# G008A.net
KiCad netlist of a schematic drawn in EAGLE
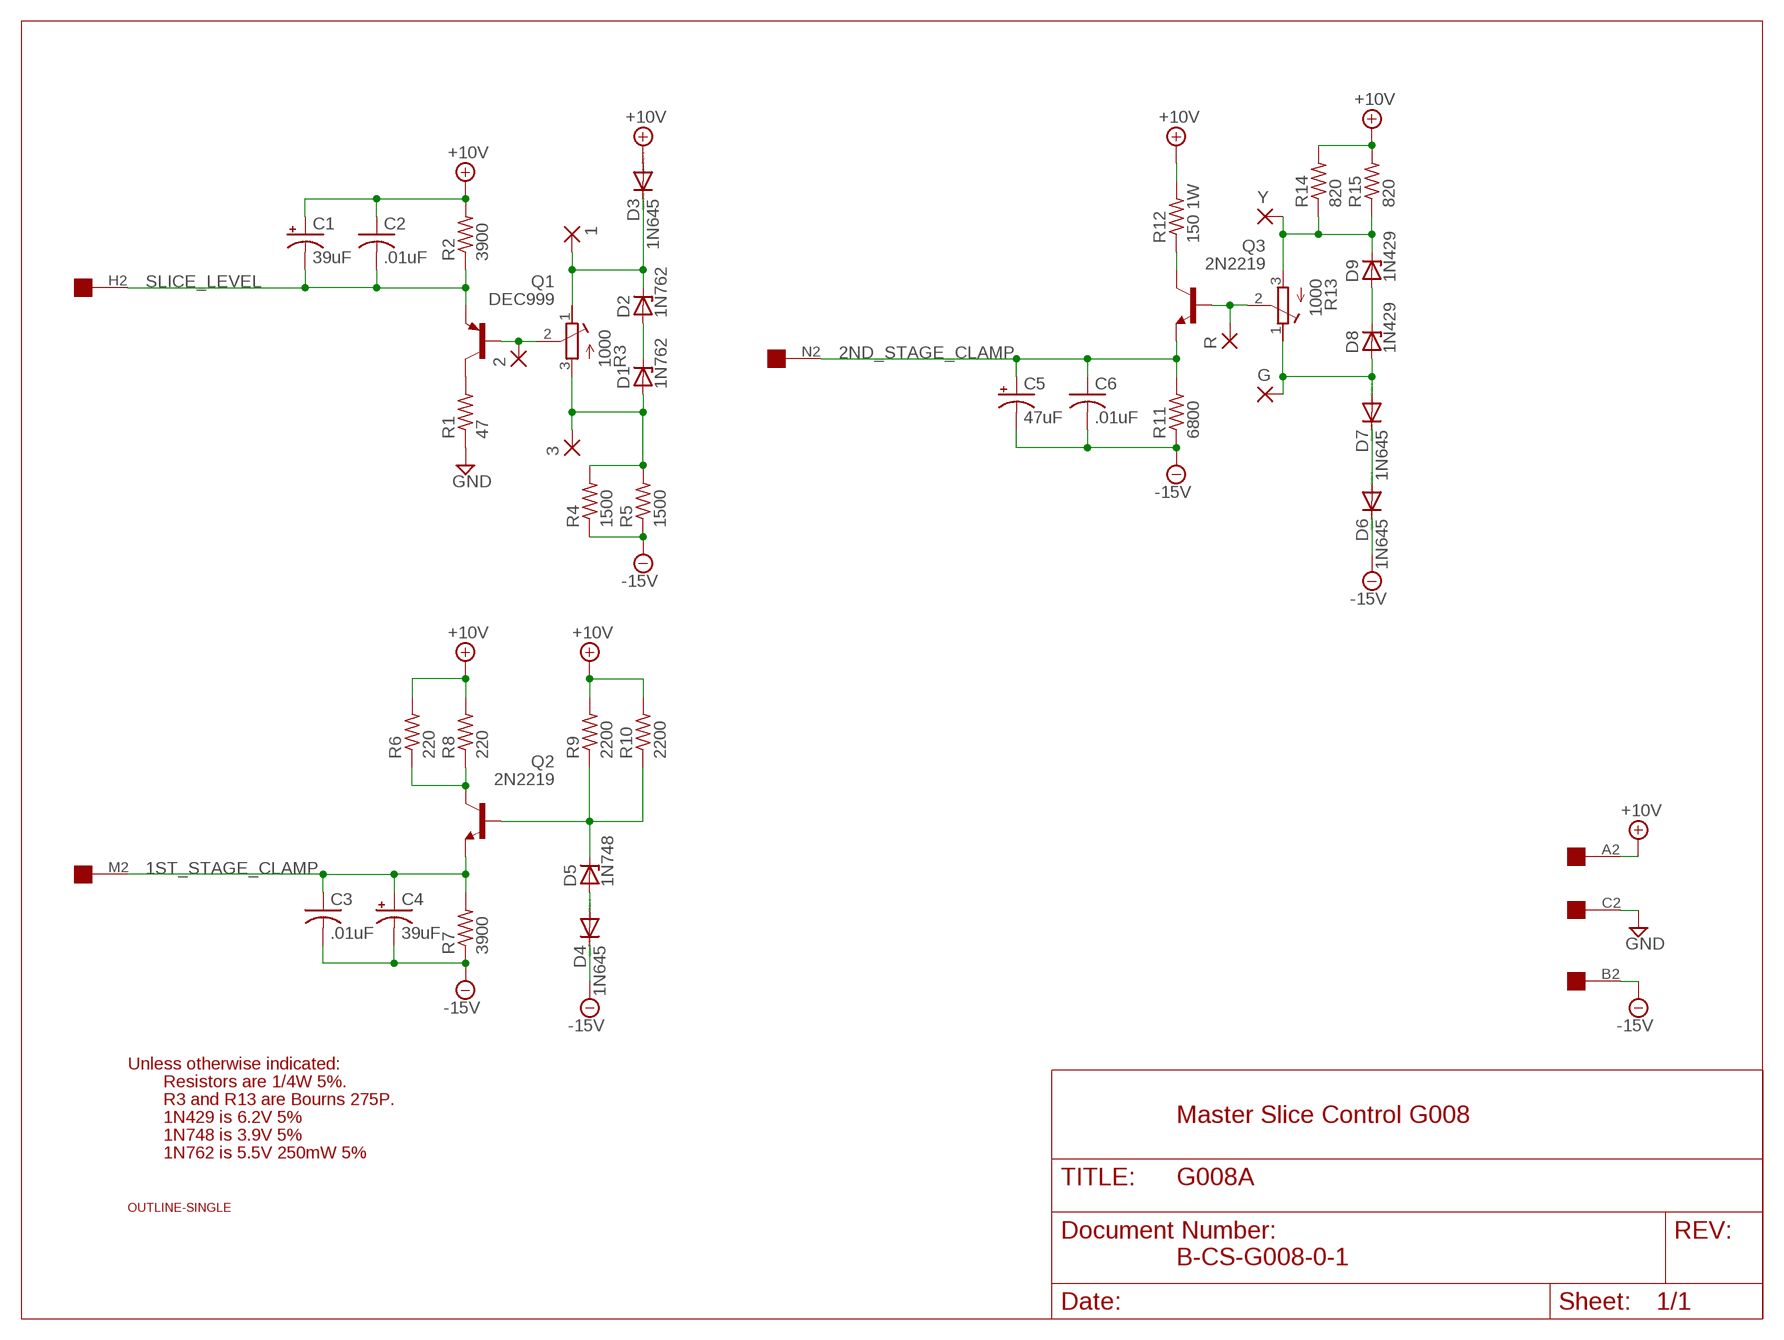
[diagram p0: schematic, sheet 1]

(export (version "E")
  (design (tool "Eeschema 10.0.6"))
  (components
    (comp (ref "1")
      (value "2,54/0,8")
      (footprint "eagle-import:2,54_0,8")
      (libsource (lib "eagle-import") (part "2,54/0,8"))
    )
    (comp (ref "2")
      (value "2,54/0,8")
      (footprint "eagle-import:2,54_0,8")
      (libsource (lib "eagle-import") (part "2,54/0,8"))
    )
    (comp (ref "3")
      (value "2,54/0,8")
      (footprint "eagle-import:2,54_0,8")
      (libsource (lib "eagle-import") (part "2,54/0,8"))
    )
    (comp (ref "C1")
      (value "39uF")
      (footprint "eagle-import:E15-5")
      (libsource (lib "eagle-import") (part "CPOL-USE15-5AXIAL"))
    )
    (comp (ref "C2")
      (value ".01uF")
      (footprint "eagle-import:C050-025X075")
      (libsource (lib "eagle-import") (part "C-US050-025X075"))
    )
    (comp (ref "C3")
      (value ".01uF")
      (footprint "eagle-import:C050-025X075")
      (libsource (lib "eagle-import") (part "C-US050-025X075"))
    )
    (comp (ref "C4")
      (value "39uF")
      (footprint "eagle-import:E15-5")
      (libsource (lib "eagle-import") (part "CPOL-USE15-5AXIAL"))
    )
    (comp (ref "C5")
      (value "47uF")
      (footprint "eagle-import:E22-6")
      (libsource (lib "eagle-import") (part "CPOL-USE22-6AXIAL"))
    )
    (comp (ref "C6")
      (value ".01uF")
      (footprint "eagle-import:C050-025X075")
      (libsource (lib "eagle-import") (part "C-US050-025X075"))
    )
    (comp (ref "D1")
      (value "1N762")
      (footprint "eagle-import:DO35Z10")
      (libsource (lib "eagle-import") (part "ZENER-DIODEDO35Z10"))
    )
    (comp (ref "D2")
      (value "1N762")
      (footprint "eagle-import:DO35Z10")
      (libsource (lib "eagle-import") (part "ZENER-DIODEDO35Z10"))
    )
    (comp (ref "D3")
      (value "1N645")
      (footprint "eagle-import:DO35-10")
      (libsource (lib "eagle-import") (part "1N4148DO35-10"))
    )
    (comp (ref "D4")
      (value "1N645")
      (footprint "eagle-import:DO35-10")
      (libsource (lib "eagle-import") (part "1N4148DO35-10"))
    )
    (comp (ref "D5")
      (value "1N748")
      (footprint "eagle-import:DO35Z10")
      (libsource (lib "eagle-import") (part "ZENER-DIODEDO35Z10"))
    )
    (comp (ref "D6")
      (value "1N645")
      (footprint "eagle-import:DO35-10")
      (libsource (lib "eagle-import") (part "1N4148DO35-10"))
    )
    (comp (ref "D7")
      (value "1N645")
      (footprint "eagle-import:DO35-10")
      (libsource (lib "eagle-import") (part "1N4148DO35-10"))
    )
    (comp (ref "D8")
      (value "1N429")
      (footprint "eagle-import:DO35Z10")
      (libsource (lib "eagle-import") (part "ZENER-DIODEDO35Z10"))
    )
    (comp (ref "D9")
      (value "1N429")
      (footprint "eagle-import:DO35Z10")
      (libsource (lib "eagle-import") (part "ZENER-DIODEDO35Z10"))
    )
    (comp (ref "G")
      (value "2,54/0,8")
      (footprint "eagle-import:2,54_0,8")
      (libsource (lib "eagle-import") (part "2,54/0,8"))
    )
    (comp (ref "Q1")
      (value "DEC999")
      (footprint "eagle-import:TO39")
      (libsource (lib "eagle-import") (part "2N2904"))
    )
    (comp (ref "Q2")
      (value "2N2219")
      (footprint "eagle-import:TO5")
      (libsource (lib "eagle-import") (part "2N2102"))
    )
    (comp (ref "Q3")
      (value "2N2219")
      (footprint "eagle-import:TO5")
      (libsource (lib "eagle-import") (part "2N2102"))
    )
    (comp (ref "R")
      (value "2,54/0,8")
      (footprint "eagle-import:2,54_0,8")
      (libsource (lib "eagle-import") (part "2,54/0,8"))
    )
    (comp (ref "R1")
      (value "47")
      (footprint "eagle-import:0207_10")
      (libsource (lib "eagle-import") (part "R-US_0207/10"))
    )
    (comp (ref "R2")
      (value "3900")
      (footprint "eagle-import:0207_10")
      (libsource (lib "eagle-import") (part "R-US_0207/10"))
    )
    (comp (ref "R3")
      (value "1000")
      (footprint "eagle-import:3006Y")
      (libsource (lib "eagle-import") (part "275P"))
    )
    (comp (ref "R4")
      (value "1500")
      (footprint "eagle-import:0207_10")
      (libsource (lib "eagle-import") (part "R-US_0207/10"))
    )
    (comp (ref "R5")
      (value "1500")
      (footprint "eagle-import:0207_10")
      (libsource (lib "eagle-import") (part "R-US_0207/10"))
    )
    (comp (ref "R6")
      (value "220")
      (footprint "eagle-import:0207_10")
      (libsource (lib "eagle-import") (part "R-US_0207/10"))
    )
    (comp (ref "R7")
      (value "3900")
      (footprint "eagle-import:0207_10")
      (libsource (lib "eagle-import") (part "R-US_0207/10"))
    )
    (comp (ref "R8")
      (value "220")
      (footprint "eagle-import:0207_10")
      (libsource (lib "eagle-import") (part "R-US_0207/10"))
    )
    (comp (ref "R9")
      (value "2200")
      (footprint "eagle-import:0207_10")
      (libsource (lib "eagle-import") (part "R-US_0207/10"))
    )
    (comp (ref "R10")
      (value "2200")
      (footprint "eagle-import:0207_10")
      (libsource (lib "eagle-import") (part "R-US_0207/10"))
    )
    (comp (ref "R11")
      (value "6800")
      (footprint "eagle-import:0207_10")
      (libsource (lib "eagle-import") (part "R-US_0207/10"))
    )
    (comp (ref "R12")
      (value "150 1W")
      (footprint "eagle-import:0617_22")
      (libsource (lib "eagle-import") (part "R-US_0617/22"))
    )
    (comp (ref "R13")
      (value "1000")
      (footprint "eagle-import:3006Y")
      (libsource (lib "eagle-import") (part "275P"))
    )
    (comp (ref "R14")
      (value "820")
      (footprint "eagle-import:0207_10")
      (libsource (lib "eagle-import") (part "R-US_0207/10"))
    )
    (comp (ref "R15")
      (value "820")
      (footprint "eagle-import:0207_10")
      (libsource (lib "eagle-import") (part "R-US_0207/10"))
    )
    (comp (ref "U$1")
      (value "OUTLINE-SINGLE")
      (footprint "eagle-import:SINGLE")
      (libsource (lib "eagle-import") (part "OUTLINE-SINGLE"))
    )
    (comp (ref "U$2")
      (value "EDGE-1")
      (footprint "eagle-import:EDGE-CON1")
      (libsource (lib "eagle-import") (part "EDGE-1"))
    )
    (comp (ref "Y")
      (value "2,54/0,8")
      (footprint "eagle-import:2,54_0,8")
      (libsource (lib "eagle-import") (part "2,54/0,8"))
    )
  )
  (nets
    (net (code "1") (name "+10V") (class "Default")
      (node (ref "C1") (pin "+") (pinfunction "+_+") (pintype "passive"))
      (node (ref "C2") (pin "1") (pinfunction "1_1") (pintype "passive"))
      (node (ref "D3") (pin "A") (pinfunction "A_A") (pintype "passive"))
      (node (ref "R10") (pin "2") (pinfunction "2_2") (pintype "passive"))
      (node (ref "R12") (pin "2") (pinfunction "2_2") (pintype "passive"))
      (node (ref "R14") (pin "2") (pinfunction "2_2") (pintype "passive"))
      (node (ref "R15") (pin "2") (pinfunction "2_2") (pintype "passive"))
      (node (ref "R2") (pin "2") (pinfunction "2_2") (pintype "passive"))
      (node (ref "R6") (pin "2") (pinfunction "2_2") (pintype "passive"))
      (node (ref "R8") (pin "2") (pinfunction "2_2") (pintype "passive"))
      (node (ref "R9") (pin "2") (pinfunction "2_2") (pintype "passive"))
      (node (ref "U$2") (pin "A2") (pinfunction "1_A2") (pintype "bidirectional"))
    )
    (net (code "2") (name "-15V") (class "Default")
      (node (ref "C3") (pin "2") (pinfunction "2_2") (pintype "passive"))
      (node (ref "C4") (pin "-") (pinfunction "-_-") (pintype "passive"))
      (node (ref "C5") (pin "-") (pinfunction "-_-") (pintype "passive"))
      (node (ref "C6") (pin "2") (pinfunction "2_2") (pintype "passive"))
      (node (ref "D4") (pin "C") (pinfunction "C_C") (pintype "passive"))
      (node (ref "D6") (pin "C") (pinfunction "C_C") (pintype "passive"))
      (node (ref "R11") (pin "1") (pinfunction "1_1") (pintype "passive"))
      (node (ref "R4") (pin "1") (pinfunction "1_1") (pintype "passive"))
      (node (ref "R5") (pin "1") (pinfunction "1_1") (pintype "passive"))
      (node (ref "R7") (pin "1") (pinfunction "1_1") (pintype "passive"))
      (node (ref "U$2") (pin "B2") (pinfunction "1_B2") (pintype "bidirectional"))
    )
    (net (code "3") (name "/1ST_STAGE_CLAMP") (class "Default")
      (node (ref "C3") (pin "1") (pinfunction "1_1") (pintype "passive"))
      (node (ref "C4") (pin "+") (pinfunction "+_+") (pintype "passive"))
      (node (ref "Q2") (pin "1") (pinfunction "E_1") (pintype "passive"))
      (node (ref "R7") (pin "2") (pinfunction "2_2") (pintype "passive"))
      (node (ref "U$2") (pin "M2") (pinfunction "1_M2") (pintype "bidirectional"))
    )
    (net (code "4") (name "/2ND_STAGE_CLAMP") (class "Default")
      (node (ref "C5") (pin "+") (pinfunction "+_+") (pintype "passive"))
      (node (ref "C6") (pin "1") (pinfunction "1_1") (pintype "passive"))
      (node (ref "Q3") (pin "1") (pinfunction "E_1") (pintype "passive"))
      (node (ref "R11") (pin "2") (pinfunction "2_2") (pintype "passive"))
      (node (ref "U$2") (pin "N2") (pinfunction "1_N2") (pintype "bidirectional"))
    )
    (net (code "5") (name "/SLICE_LEVEL") (class "Default")
      (node (ref "C1") (pin "-") (pinfunction "-_-") (pintype "passive"))
      (node (ref "C2") (pin "2") (pinfunction "2_2") (pintype "passive"))
      (node (ref "Q1") (pin "1") (pinfunction "E_1") (pintype "passive"))
      (node (ref "R2") (pin "1") (pinfunction "1_1") (pintype "passive"))
      (node (ref "U$2") (pin "H2") (pinfunction "1_H2") (pintype "bidirectional"))
    )
    (net (code "6") (name "GND") (class "Default")
      (node (ref "R1") (pin "1") (pinfunction "1_1") (pintype "passive"))
      (node (ref "U$2") (pin "C2") (pinfunction "1_C2") (pintype "bidirectional"))
    )
    (net (code "7") (name "Net-(1-P)") (class "Default")
      (node (ref "1") (pin "1") (pinfunction "P_1") (pintype "passive"))
      (node (ref "D2") (pin "C") (pinfunction "C_C") (pintype "passive"))
      (node (ref "D3") (pin "C") (pinfunction "C_C") (pintype "passive"))
      (node (ref "R3") (pin "1") (pinfunction "A_1") (pintype "passive"))
    )
    (net (code "8") (name "Net-(2-P)") (class "Default")
      (node (ref "2") (pin "1") (pinfunction "P_1") (pintype "passive"))
      (node (ref "Q1") (pin "2") (pinfunction "B_2") (pintype "passive"))
      (node (ref "R3") (pin "2") (pinfunction "S_2") (pintype "passive"))
    )
    (net (code "9") (name "Net-(3-P)") (class "Default")
      (node (ref "3") (pin "1") (pinfunction "P_1") (pintype "passive"))
      (node (ref "D1") (pin "A") (pinfunction "A_A") (pintype "passive"))
      (node (ref "R3") (pin "3") (pinfunction "E_3") (pintype "passive"))
      (node (ref "R4") (pin "2") (pinfunction "2_2") (pintype "passive"))
      (node (ref "R5") (pin "2") (pinfunction "2_2") (pintype "passive"))
    )
    (net (code "10") (name "Net-(D1-PadC)") (class "Default")
      (node (ref "D1") (pin "C") (pinfunction "C_C") (pintype "passive"))
      (node (ref "D2") (pin "A") (pinfunction "A_A") (pintype "passive"))
    )
    (net (code "11") (name "Net-(D4-PadA)") (class "Default")
      (node (ref "D4") (pin "A") (pinfunction "A_A") (pintype "passive"))
      (node (ref "D5") (pin "A") (pinfunction "A_A") (pintype "passive"))
    )
    (net (code "12") (name "Net-(D6-PadA)") (class "Default")
      (node (ref "D6") (pin "A") (pinfunction "A_A") (pintype "passive"))
      (node (ref "D7") (pin "C") (pinfunction "C_C") (pintype "passive"))
    )
    (net (code "13") (name "Net-(D8-PadC)") (class "Default")
      (node (ref "D8") (pin "C") (pinfunction "C_C") (pintype "passive"))
      (node (ref "D9") (pin "A") (pinfunction "A_A") (pintype "passive"))
    )
    (net (code "14") (name "Net-(G-P)") (class "Default")
      (node (ref "D7") (pin "A") (pinfunction "A_A") (pintype "passive"))
      (node (ref "D8") (pin "A") (pinfunction "A_A") (pintype "passive"))
      (node (ref "G") (pin "1") (pinfunction "P_1") (pintype "passive"))
      (node (ref "R13") (pin "1") (pinfunction "A_1") (pintype "passive"))
    )
    (net (code "15") (name "Net-(Q1-C)") (class "Default")
      (node (ref "Q1") (pin "3") (pinfunction "C_3") (pintype "passive"))
      (node (ref "R1") (pin "2") (pinfunction "2_2") (pintype "passive"))
    )
    (net (code "16") (name "Net-(Q2-B)") (class "Default")
      (node (ref "D5") (pin "C") (pinfunction "C_C") (pintype "passive"))
      (node (ref "Q2") (pin "2") (pinfunction "B_2") (pintype "passive"))
      (node (ref "R10") (pin "1") (pinfunction "1_1") (pintype "passive"))
      (node (ref "R9") (pin "1") (pinfunction "1_1") (pintype "passive"))
    )
    (net (code "17") (name "Net-(Q2-C)") (class "Default")
      (node (ref "Q2") (pin "3") (pinfunction "C_3") (pintype "passive"))
      (node (ref "R6") (pin "1") (pinfunction "1_1") (pintype "passive"))
      (node (ref "R8") (pin "1") (pinfunction "1_1") (pintype "passive"))
    )
    (net (code "18") (name "Net-(Q3-B)") (class "Default")
      (node (ref "Q3") (pin "2") (pinfunction "B_2") (pintype "passive"))
      (node (ref "R") (pin "1") (pinfunction "P_1") (pintype "passive"))
      (node (ref "R13") (pin "2") (pinfunction "S_2") (pintype "passive"))
    )
    (net (code "19") (name "Net-(Q3-C)") (class "Default")
      (node (ref "Q3") (pin "3") (pinfunction "C_3") (pintype "passive"))
      (node (ref "R12") (pin "1") (pinfunction "1_1") (pintype "passive"))
    )
    (net (code "20") (name "Net-(R13-E)") (class "Default")
      (node (ref "D9") (pin "C") (pinfunction "C_C") (pintype "passive"))
      (node (ref "R13") (pin "3") (pinfunction "E_3") (pintype "passive"))
      (node (ref "R14") (pin "1") (pinfunction "1_1") (pintype "passive"))
      (node (ref "R15") (pin "1") (pinfunction "1_1") (pintype "passive"))
      (node (ref "Y") (pin "1") (pinfunction "P_1") (pintype "passive"))
    )
  )
)
